# E4m.net
KiCad netlist of a schematic drawn in EAGLE
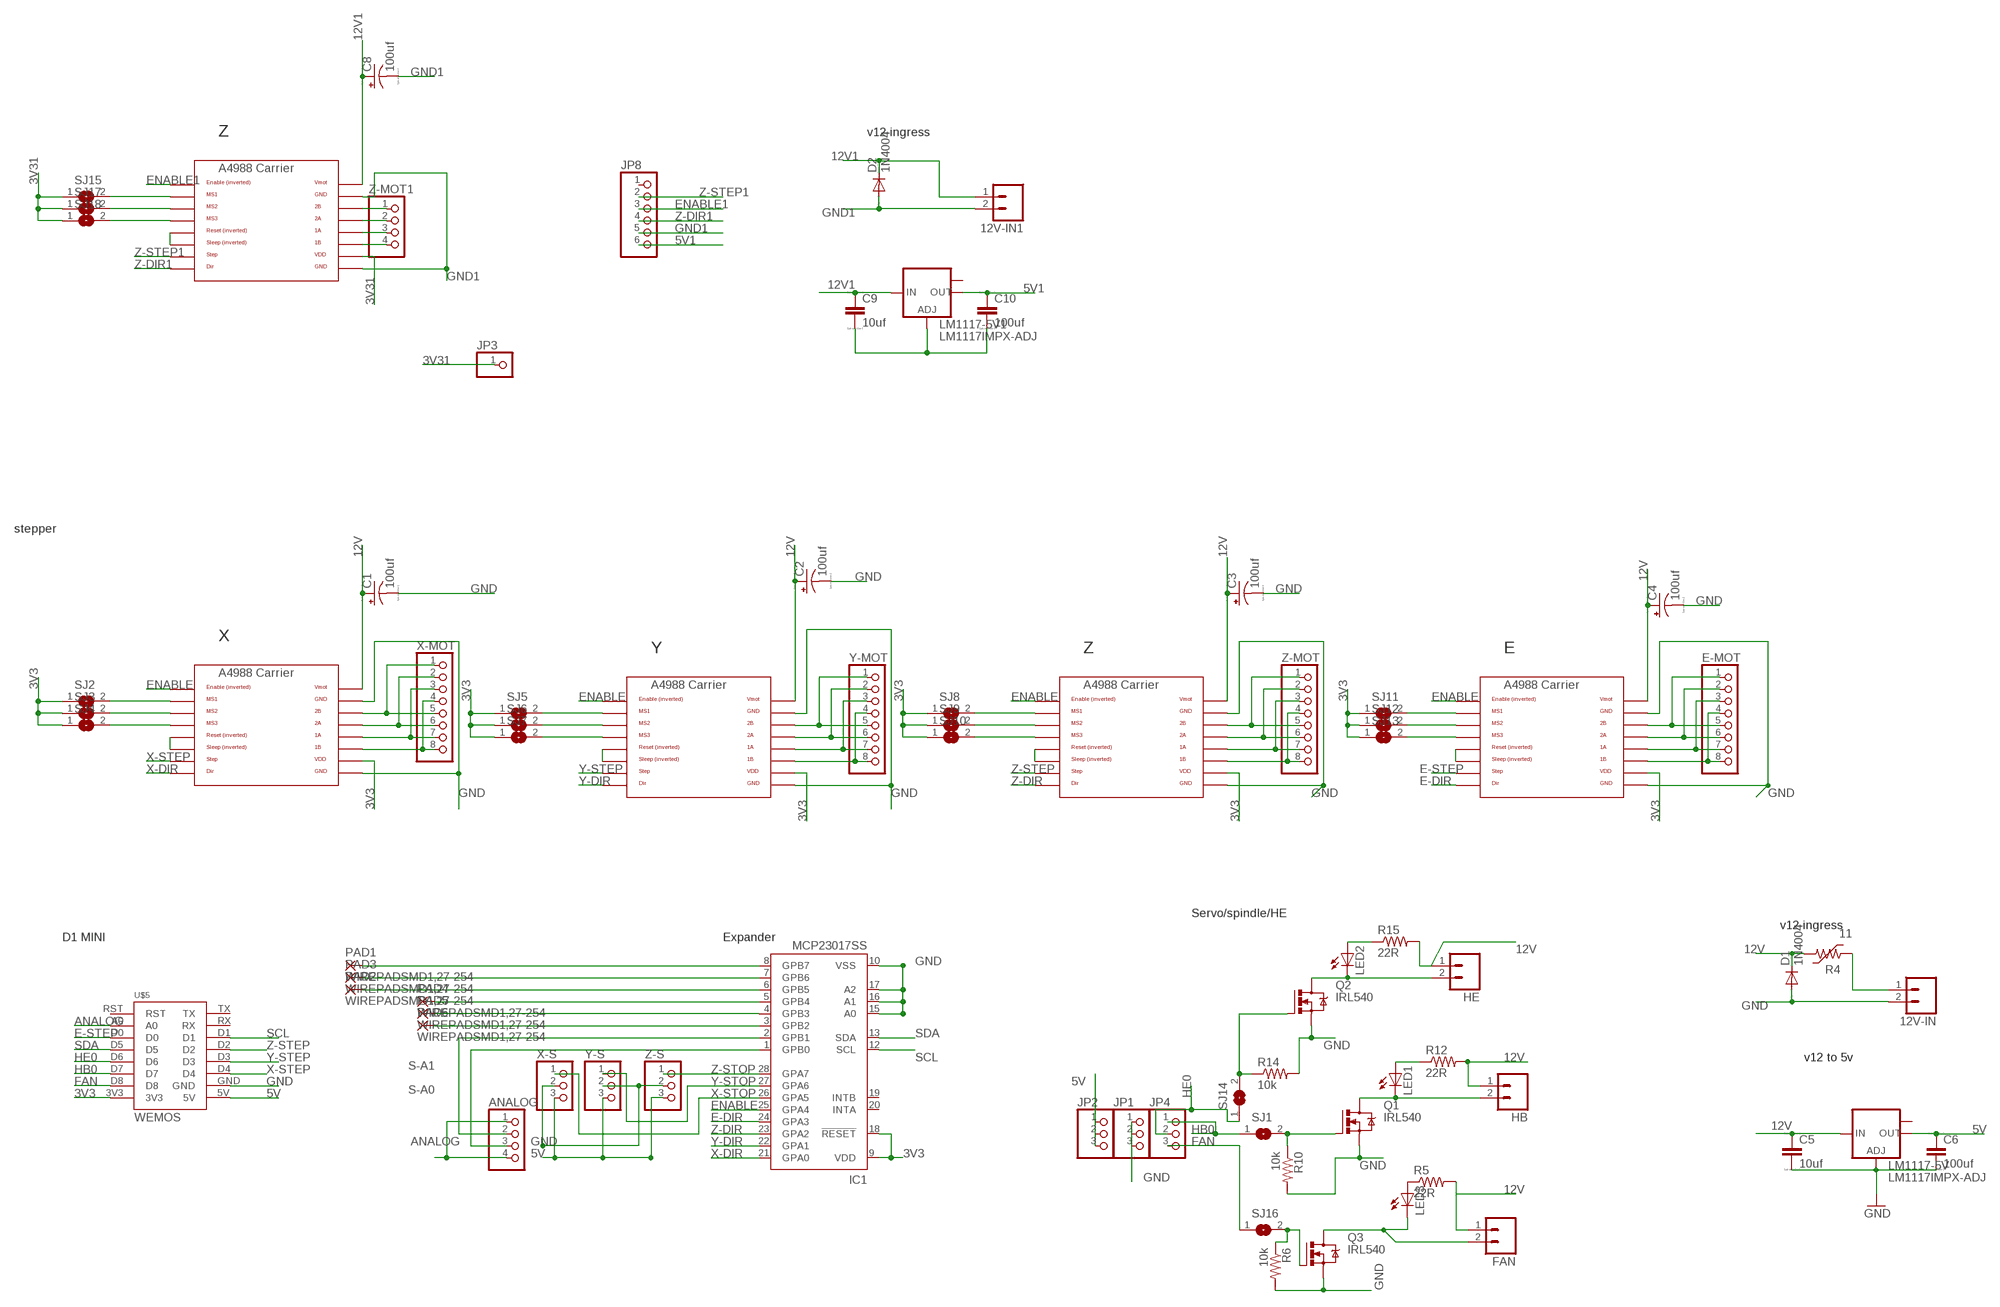
[diagram p0: schematic, sheet 1]

(export (version "E")
  (design (tool "Eeschema 10.0.6"))
  (components
    (comp (ref "12V-IN")
      (value "M02PTH")
      (footprint "eagle-import:1X02")
      (libsource (lib "eagle-import") (part "M02PTH"))
    )
    (comp (ref "12V-IN1")
      (value "M02PTH")
      (footprint "eagle-import:1X02")
      (libsource (lib "eagle-import") (part "M02PTH"))
    )
    (comp (ref "ANALOG")
      (value "PINHD-1X4")
      (footprint "eagle-import:1X04")
      (libsource (lib "eagle-import") (part "PINHD-1X4"))
    )
    (comp (ref "C1")
      (value "100uf")
      (footprint "eagle-import:153CLV-0605")
      (libsource (lib "eagle-import") (part "CPOL-US153CLV-0605"))
    )
    (comp (ref "C2")
      (value "100uf")
      (footprint "eagle-import:153CLV-0605")
      (libsource (lib "eagle-import") (part "CPOL-US153CLV-0605"))
    )
    (comp (ref "C3")
      (value "100uf")
      (footprint "eagle-import:153CLV-0605")
      (libsource (lib "eagle-import") (part "CPOL-US153CLV-0605"))
    )
    (comp (ref "C4")
      (value "100uf")
      (footprint "eagle-import:153CLV-0605")
      (libsource (lib "eagle-import") (part "CPOL-US153CLV-0605"))
    )
    (comp (ref "C5")
      (value "10uf")
      (footprint "eagle-import:C0805")
      (libsource (lib "eagle-import") (part "C"))
    )
    (comp (ref "C6")
      (value "100uf")
      (footprint "eagle-import:C0805")
      (libsource (lib "eagle-import") (part "C"))
    )
    (comp (ref "C8")
      (value "100uf")
      (footprint "eagle-import:153CLV-0605")
      (libsource (lib "eagle-import") (part "CPOL-US153CLV-0605"))
    )
    (comp (ref "C9")
      (value "10uf")
      (footprint "eagle-import:C0603")
      (libsource (lib "eagle-import") (part "CC0603"))
    )
    (comp (ref "C10")
      (value "100uf")
      (footprint "eagle-import:C0603")
      (libsource (lib "eagle-import") (part "CC0603"))
    )
    (comp (ref "D1")
      (value "1N4004")
      (footprint "eagle-import:DO41-10")
      (libsource (lib "eagle-import") (part "1N4004"))
    )
    (comp (ref "D2")
      (value "1N4004")
      (footprint "eagle-import:DO41-10")
      (libsource (lib "eagle-import") (part "1N4004"))
    )
    (comp (ref "E-MOT")
      (value "PINHD-1X8CLEANBIG")
      (footprint "eagle-import:1X08-CLEANBIG")
      (libsource (lib "eagle-import") (part "PINHD-1X8CLEANBIG"))
    )
    (comp (ref "FAN")
      (value "M02PTH")
      (footprint "eagle-import:1X02")
      (libsource (lib "eagle-import") (part "M02PTH"))
    )
    (comp (ref "HB")
      (value "M02PTH")
      (footprint "eagle-import:1X02")
      (libsource (lib "eagle-import") (part "M02PTH"))
    )
    (comp (ref "HE")
      (value "M02PTH")
      (footprint "eagle-import:1X02")
      (libsource (lib "eagle-import") (part "M02PTH"))
    )
    (comp (ref "IC1")
      (value "MCP23017SS")
      (footprint "eagle-import:SSOP28")
      (libsource (lib "eagle-import") (part "MCP23017SS"))
    )
    (comp (ref "JP1")
      (value "PINHD-1X3CB")
      (footprint "eagle-import:1X03-CLEANBIG")
      (libsource (lib "eagle-import") (part "PINHD-1X3CB"))
    )
    (comp (ref "JP2")
      (value "PINHD-1X3CB")
      (footprint "eagle-import:1X03-CLEANBIG")
      (libsource (lib "eagle-import") (part "PINHD-1X3CB"))
    )
    (comp (ref "JP3")
      (value "PINHD-1X1CB")
      (footprint "eagle-import:1X01-CLEANBIG")
      (libsource (lib "eagle-import") (part "PINHD-1X1CB"))
    )
    (comp (ref "JP4")
      (value "PINHD-1X3CB")
      (footprint "eagle-import:1X03-CLEANBIG")
      (libsource (lib "eagle-import") (part "PINHD-1X3CB"))
    )
    (comp (ref "JP8")
      (value "PINHD-1X6")
      (footprint "eagle-import:1X06")
      (libsource (lib "eagle-import") (part "PINHD-1X6"))
    )
    (comp (ref "LED1")
      (value "LEDCHIP-LED0805")
      (footprint "eagle-import:CHIP-LED0805")
      (libsource (lib "eagle-import") (part "LEDCHIP-LED0805"))
    )
    (comp (ref "LED2")
      (value "LEDCHIP-LED0805")
      (footprint "eagle-import:CHIP-LED0805")
      (libsource (lib "eagle-import") (part "LEDCHIP-LED0805"))
    )
    (comp (ref "LED3")
      (value "LEDCHIP-LED0805")
      (footprint "eagle-import:CHIP-LED0805")
      (libsource (lib "eagle-import") (part "LEDCHIP-LED0805"))
    )
    (comp (ref "LM1117-5V")
      (value "LM1117IMPX-ADJ")
      (footprint "eagle-import:SOT223")
      (libsource (lib "eagle-import") (part "LM1117IMPX-ADJ"))
    )
    (comp (ref "LM1117-5V1")
      (value "LM1117IMPX-ADJ")
      (footprint "eagle-import:SOT223")
      (libsource (lib "eagle-import") (part "LM1117IMPX-ADJ"))
    )
    (comp (ref "PAD1")
      (value "WIREPADSMD1,27-254")
      (footprint "eagle-import:SMD1,27-2,54")
      (libsource (lib "eagle-import") (part "WIREPADSMD1,27-254"))
    )
    (comp (ref "PAD2")
      (value "WIREPADSMD1,27-254")
      (footprint "eagle-import:SMD1,27-2,54")
      (libsource (lib "eagle-import") (part "WIREPADSMD1,27-254"))
    )
    (comp (ref "PAD3")
      (value "WIREPADSMD1,27-254")
      (footprint "eagle-import:SMD1,27-2,54")
      (libsource (lib "eagle-import") (part "WIREPADSMD1,27-254"))
    )
    (comp (ref "PAD4")
      (value "WIREPADSMD1,27-254")
      (footprint "eagle-import:SMD1,27-2,54")
      (libsource (lib "eagle-import") (part "WIREPADSMD1,27-254"))
    )
    (comp (ref "PAD5")
      (value "WIREPADSMD1,27-254")
      (footprint "eagle-import:SMD1,27-2,54")
      (libsource (lib "eagle-import") (part "WIREPADSMD1,27-254"))
    )
    (comp (ref "PAD6")
      (value "WIREPADSMD1,27-254")
      (footprint "eagle-import:SMD1,27-2,54")
      (libsource (lib "eagle-import") (part "WIREPADSMD1,27-254"))
    )
    (comp (ref "Q1")
      (value "IRL540")
      (footprint "eagle-import:TO220BV")
      (libsource (lib "eagle-import") (part "IRF540"))
    )
    (comp (ref "Q2")
      (value "IRL540")
      (footprint "eagle-import:TO220BV")
      (libsource (lib "eagle-import") (part "IRF540"))
    )
    (comp (ref "Q3")
      (value "IRL540")
      (footprint "eagle-import:TO220BV")
      (libsource (lib "eagle-import") (part "IRF540"))
    )
    (comp (ref "R4")
      (value "11")
      (footprint "eagle-import:PF-8.0")
      (libsource (lib "eagle-import") (part "PTC-PF-8.0"))
    )
    (comp (ref "R5")
      (value "22R")
      (footprint "eagle-import:R0805")
      (libsource (lib "eagle-import") (part "R-US_R0805"))
    )
    (comp (ref "R6")
      (value "10k")
      (footprint "eagle-import:R0805")
      (libsource (lib "eagle-import") (part "R-US_R0805"))
    )
    (comp (ref "R10")
      (value "10k")
      (footprint "eagle-import:R0805")
      (libsource (lib "eagle-import") (part "R-US_R0805"))
    )
    (comp (ref "R12")
      (value "22R")
      (footprint "eagle-import:R0805")
      (libsource (lib "eagle-import") (part "R-US_R0805"))
    )
    (comp (ref "R14")
      (value "10k")
      (footprint "eagle-import:R0805")
      (libsource (lib "eagle-import") (part "R-US_R0805"))
    )
    (comp (ref "R15")
      (value "22R")
      (footprint "eagle-import:R0805")
      (libsource (lib "eagle-import") (part "R-US_R0805"))
    )
    (comp (ref "SJ1") (value "SJ") (footprint "eagle-import:SJ") (libsource (lib "eagle-import") (part "SJ")))
    (comp (ref "SJ2") (value "SJ") (footprint "eagle-import:SJ") (libsource (lib "eagle-import") (part "SJ")))
    (comp (ref "SJ3") (value "SJ") (footprint "eagle-import:SJ") (libsource (lib "eagle-import") (part "SJ")))
    (comp (ref "SJ4") (value "SJ") (footprint "eagle-import:SJ") (libsource (lib "eagle-import") (part "SJ")))
    (comp (ref "SJ5") (value "SJ") (footprint "eagle-import:SJ") (libsource (lib "eagle-import") (part "SJ")))
    (comp (ref "SJ6") (value "SJ") (footprint "eagle-import:SJ") (libsource (lib "eagle-import") (part "SJ")))
    (comp (ref "SJ7") (value "SJ") (footprint "eagle-import:SJ") (libsource (lib "eagle-import") (part "SJ")))
    (comp (ref "SJ8") (value "SJ") (footprint "eagle-import:SJ") (libsource (lib "eagle-import") (part "SJ")))
    (comp (ref "SJ9") (value "SJ") (footprint "eagle-import:SJ") (libsource (lib "eagle-import") (part "SJ")))
    (comp (ref "SJ10")
      (value "SJ")
      (footprint "eagle-import:SJ")
      (libsource (lib "eagle-import") (part "SJ"))
    )
    (comp (ref "SJ11")
      (value "SJ")
      (footprint "eagle-import:SJ")
      (libsource (lib "eagle-import") (part "SJ"))
    )
    (comp (ref "SJ12")
      (value "SJ")
      (footprint "eagle-import:SJ")
      (libsource (lib "eagle-import") (part "SJ"))
    )
    (comp (ref "SJ13")
      (value "SJ")
      (footprint "eagle-import:SJ")
      (libsource (lib "eagle-import") (part "SJ"))
    )
    (comp (ref "SJ14")
      (value "SJ")
      (footprint "eagle-import:SJ")
      (libsource (lib "eagle-import") (part "SJ"))
    )
    (comp (ref "SJ15")
      (value "SJ")
      (footprint "eagle-import:SJ")
      (libsource (lib "eagle-import") (part "SJ"))
    )
    (comp (ref "SJ16")
      (value "SJ")
      (footprint "eagle-import:SJ")
      (libsource (lib "eagle-import") (part "SJ"))
    )
    (comp (ref "SJ17")
      (value "SJ")
      (footprint "eagle-import:SJ")
      (libsource (lib "eagle-import") (part "SJ"))
    )
    (comp (ref "SJ18")
      (value "SJ")
      (footprint "eagle-import:SJ")
      (libsource (lib "eagle-import") (part "SJ"))
    )
    (comp (ref "U$1")
      (value "A4988BREAKOUT")
      (footprint "eagle-import:A4988BREAKOUT")
      (libsource (lib "eagle-import") (part "A4988BREAKOUT"))
    )
    (comp (ref "U$2")
      (value "A4988BREAKOUT")
      (footprint "eagle-import:A4988BREAKOUT")
      (libsource (lib "eagle-import") (part "A4988BREAKOUT"))
    )
    (comp (ref "U$3")
      (value "A4988BREAKOUT")
      (footprint "eagle-import:A4988BREAKOUT")
      (libsource (lib "eagle-import") (part "A4988BREAKOUT"))
    )
    (comp (ref "U$5")
      (value "WEMOS")
      (footprint "eagle-import:WEMOS")
      (libsource (lib "eagle-import") (part "WEMOS"))
    )
    (comp (ref "U$6")
      (value "A4988BREAKOUT")
      (footprint "eagle-import:A4988BREAKOUT")
      (libsource (lib "eagle-import") (part "A4988BREAKOUT"))
    )
    (comp (ref "U$9")
      (value "A4988BREAKOUT")
      (footprint "eagle-import:A4988BREAKOUT")
      (libsource (lib "eagle-import") (part "A4988BREAKOUT"))
    )
    (comp (ref "X-MOT")
      (value "PINHD-1X8CLEANBIG")
      (footprint "eagle-import:1X08-CLEANBIG")
      (libsource (lib "eagle-import") (part "PINHD-1X8CLEANBIG"))
    )
    (comp (ref "X-S")
      (value "PINHD-1X3CB")
      (footprint "eagle-import:1X03-CLEANBIG")
      (libsource (lib "eagle-import") (part "PINHD-1X3CB"))
    )
    (comp (ref "Y-MOT")
      (value "PINHD-1X8CLEANBIG")
      (footprint "eagle-import:1X08-CLEANBIG")
      (libsource (lib "eagle-import") (part "PINHD-1X8CLEANBIG"))
    )
    (comp (ref "Y-S")
      (value "PINHD-1X3CB")
      (footprint "eagle-import:1X03-CLEANBIG")
      (libsource (lib "eagle-import") (part "PINHD-1X3CB"))
    )
    (comp (ref "Z-MOT")
      (value "PINHD-1X8CLEANBIG")
      (footprint "eagle-import:1X08-CLEANBIG")
      (libsource (lib "eagle-import") (part "PINHD-1X8CLEANBIG"))
    )
    (comp (ref "Z-MOT1")
      (value "PINHD-1X4")
      (footprint "eagle-import:1X04")
      (libsource (lib "eagle-import") (part "PINHD-1X4"))
    )
    (comp (ref "Z-S")
      (value "PINHD-1X3CB")
      (footprint "eagle-import:1X03-CLEANBIG")
      (libsource (lib "eagle-import") (part "PINHD-1X3CB"))
    )
  )
  (nets
    (net (code "1") (name "/3V3") (class "Default")
      (node (ref "IC1") (pin "18") (pinfunction "~{RESET}_18") (pintype "input"))
      (node (ref "IC1") (pin "9") (pinfunction "VDD_9") (pintype "power_in"))
      (node (ref "SJ10") (pin "1") (pinfunction "1_1") (pintype "passive"))
      (node (ref "SJ11") (pin "1") (pinfunction "1_1") (pintype "passive"))
      (node (ref "SJ12") (pin "1") (pinfunction "1_1") (pintype "passive"))
      (node (ref "SJ13") (pin "1") (pinfunction "1_1") (pintype "passive"))
      (node (ref "SJ2") (pin "1") (pinfunction "1_1") (pintype "passive"))
      (node (ref "SJ3") (pin "1") (pinfunction "1_1") (pintype "passive"))
      (node (ref "SJ4") (pin "1") (pinfunction "1_1") (pintype "passive"))
      (node (ref "SJ5") (pin "1") (pinfunction "1_1") (pintype "passive"))
      (node (ref "SJ6") (pin "1") (pinfunction "1_1") (pintype "passive"))
      (node (ref "SJ7") (pin "1") (pinfunction "1_1") (pintype "passive"))
      (node (ref "SJ8") (pin "1") (pinfunction "1_1") (pintype "passive"))
      (node (ref "SJ9") (pin "1") (pinfunction "1_1") (pintype "passive"))
      (node (ref "U$1") (pin "VDD") (pinfunction "VDD_VDD") (pintype "power_in"))
      (node (ref "U$2") (pin "VDD") (pinfunction "VDD_VDD") (pintype "power_in"))
      (node (ref "U$3") (pin "VDD") (pinfunction "VDD_VDD") (pintype "power_in"))
      (node (ref "U$5") (pin "3V3") (pinfunction "3V3_3V3") (pintype "bidirectional"))
      (node (ref "U$9") (pin "VDD") (pinfunction "VDD_VDD") (pintype "power_in"))
    )
    (net (code "2") (name "/3V31") (class "Default")
      (node (ref "JP3") (pin "1") (pinfunction "1_1") (pintype "passive"))
      (node (ref "SJ15") (pin "1") (pinfunction "1_1") (pintype "passive"))
      (node (ref "SJ17") (pin "1") (pinfunction "1_1") (pintype "passive"))
      (node (ref "SJ18") (pin "1") (pinfunction "1_1") (pintype "passive"))
      (node (ref "U$6") (pin "VDD") (pinfunction "VDD_VDD") (pintype "power_in"))
    )
    (net (code "3") (name "/5V") (class "Default")
      (node (ref "C6") (pin "1") (pinfunction "1_1") (pintype "passive"))
      (node (ref "JP2") (pin "1") (pinfunction "1_1") (pintype "passive"))
      (node (ref "JP2") (pin "2") (pinfunction "2_2") (pintype "passive"))
      (node (ref "JP2") (pin "3") (pinfunction "3_3") (pintype "passive"))
      (node (ref "LM1117-5V") (pin "2") (pinfunction "OUT_2") (pintype "passive"))
      (node (ref "U$5") (pin "5V") (pinfunction "5V_5V") (pintype "bidirectional"))
      (node (ref "X-S") (pin "3") (pinfunction "3_3") (pintype "passive"))
      (node (ref "Y-S") (pin "3") (pinfunction "3_3") (pintype "passive"))
      (node (ref "Z-S") (pin "3") (pinfunction "3_3") (pintype "passive"))
    )
    (net (code "4") (name "/5V1") (class "Default")
      (node (ref "C10") (pin "1") (pinfunction "1_1") (pintype "passive"))
      (node (ref "JP8") (pin "6") (pinfunction "6_6") (pintype "passive"))
      (node (ref "LM1117-5V1") (pin "2") (pinfunction "OUT_2") (pintype "passive"))
    )
    (net (code "5") (name "/12V") (class "Default")
      (node (ref "C1") (pin "+") (pinfunction "+_+") (pintype "passive"))
      (node (ref "C2") (pin "+") (pinfunction "+_+") (pintype "passive"))
      (node (ref "C3") (pin "+") (pinfunction "+_+") (pintype "passive"))
      (node (ref "C4") (pin "+") (pinfunction "+_+") (pintype "passive"))
      (node (ref "C5") (pin "1") (pinfunction "1_1") (pintype "passive"))
      (node (ref "D1") (pin "C") (pinfunction "C_C") (pintype "passive"))
      (node (ref "FAN") (pin "1") (pinfunction "1_1") (pintype "passive"))
      (node (ref "HB") (pin "1") (pinfunction "1_1") (pintype "passive"))
      (node (ref "HE") (pin "1") (pinfunction "1_1") (pintype "passive"))
      (node (ref "LM1117-5V") (pin "3") (pinfunction "IN_3") (pintype "input"))
      (node (ref "R12") (pin "2") (pinfunction "2_2") (pintype "passive"))
      (node (ref "R15") (pin "2") (pinfunction "2_2") (pintype "passive"))
      (node (ref "R4") (pin "2") (pinfunction "2_2") (pintype "passive"))
      (node (ref "R5") (pin "2") (pinfunction "2_2") (pintype "passive"))
      (node (ref "U$1") (pin "VMOT") (pinfunction "VMOT_VMOT") (pintype "power_in"))
      (node (ref "U$2") (pin "VMOT") (pinfunction "VMOT_VMOT") (pintype "power_in"))
      (node (ref "U$3") (pin "VMOT") (pinfunction "VMOT_VMOT") (pintype "power_in"))
      (node (ref "U$9") (pin "VMOT") (pinfunction "VMOT_VMOT") (pintype "power_in"))
    )
    (net (code "6") (name "/12V1") (class "Default")
      (node (ref "12V-IN1") (pin "1") (pinfunction "1_1") (pintype "passive"))
      (node (ref "C8") (pin "+") (pinfunction "+_+") (pintype "passive"))
      (node (ref "C9") (pin "1") (pinfunction "1_1") (pintype "passive"))
      (node (ref "D2") (pin "C") (pinfunction "C_C") (pintype "passive"))
      (node (ref "LM1117-5V1") (pin "3") (pinfunction "IN_3") (pintype "input"))
      (node (ref "U$6") (pin "VMOT") (pinfunction "VMOT_VMOT") (pintype "power_in"))
    )
    (net (code "7") (name "/ANALOG") (class "Default")
      (node (ref "ANALOG") (pin "1") (pinfunction "1_1") (pintype "passive"))
      (node (ref "ANALOG") (pin "4") (pinfunction "4_4") (pintype "passive"))
      (node (ref "U$5") (pin "A0") (pinfunction "A0_A0") (pintype "bidirectional"))
    )
    (net (code "8") (name "/E-DIR") (class "Default")
      (node (ref "IC1") (pin "24") (pinfunction "GPA3_24") (pintype "bidirectional"))
      (node (ref "U$2") (pin "DIR") (pinfunction "DIR_DIR") (pintype "input"))
    )
    (net (code "9") (name "/E-STEP") (class "Default")
      (node (ref "U$2") (pin "STEP") (pinfunction "STEP_STEP") (pintype "input"))
      (node (ref "U$5") (pin "D0") (pinfunction "D0_D0") (pintype "bidirectional"))
    )
    (net (code "10") (name "/ENABLE") (class "Default")
      (node (ref "IC1") (pin "25") (pinfunction "GPA4_25") (pintype "bidirectional"))
      (node (ref "U$1") (pin "EN") (pinfunction "EN_EN") (pintype "input"))
      (node (ref "U$2") (pin "EN") (pinfunction "EN_EN") (pintype "input"))
      (node (ref "U$3") (pin "EN") (pinfunction "EN_EN") (pintype "input"))
      (node (ref "U$9") (pin "EN") (pinfunction "EN_EN") (pintype "input"))
    )
    (net (code "11") (name "/ENABLE1") (class "Default")
      (node (ref "JP8") (pin "3") (pinfunction "3_3") (pintype "passive"))
      (node (ref "U$6") (pin "EN") (pinfunction "EN_EN") (pintype "input"))
    )
    (net (code "12") (name "/FAN") (class "Default")
      (node (ref "JP4") (pin "3") (pinfunction "3_3") (pintype "passive"))
      (node (ref "SJ16") (pin "1") (pinfunction "1_1") (pintype "passive"))
      (node (ref "U$5") (pin "D8") (pinfunction "D8_D8") (pintype "bidirectional"))
    )
    (net (code "13") (name "/GND1") (class "Default")
      (node (ref "12V-IN1") (pin "2") (pinfunction "2_2") (pintype "passive"))
      (node (ref "C8") (pin "-") (pinfunction "-_-") (pintype "passive"))
      (node (ref "D2") (pin "A") (pinfunction "A_A") (pintype "passive"))
      (node (ref "JP8") (pin "5") (pinfunction "5_5") (pintype "passive"))
      (node (ref "U$6") (pin "GND") (pinfunction "GND_GND") (pintype "power_in"))
      (node (ref "U$6") (pin "GND@0") (pinfunction "GND_GND@0") (pintype "power_in"))
    )
    (net (code "14") (name "/HB0") (class "Default")
      (node (ref "JP4") (pin "1") (pinfunction "1_1") (pintype "passive"))
      (node (ref "SJ1") (pin "1") (pinfunction "1_1") (pintype "passive"))
      (node (ref "U$5") (pin "D7") (pinfunction "D7_D7") (pintype "bidirectional"))
    )
    (net (code "15") (name "/HE0") (class "Default")
      (node (ref "JP4") (pin "2") (pinfunction "2_2") (pintype "passive"))
      (node (ref "SJ14") (pin "1") (pinfunction "1_1") (pintype "passive"))
      (node (ref "U$5") (pin "D6") (pinfunction "D6_D6") (pintype "bidirectional"))
    )
    (net (code "16") (name "/S-A0") (class "Default")
      (node (ref "ANALOG") (pin "3") (pinfunction "3_3") (pintype "passive"))
      (node (ref "IC1") (pin "1") (pinfunction "GPB0_1") (pintype "bidirectional"))
    )
    (net (code "17") (name "/S-A1") (class "Default")
      (node (ref "ANALOG") (pin "2") (pinfunction "2_2") (pintype "passive"))
      (node (ref "IC1") (pin "2") (pinfunction "GPB1_2") (pintype "bidirectional"))
    )
    (net (code "18") (name "/SCL") (class "Default")
      (node (ref "IC1") (pin "12") (pinfunction "SCL_12") (pintype "input"))
      (node (ref "U$5") (pin "D1") (pinfunction "D1_D1") (pintype "bidirectional"))
    )
    (net (code "19") (name "/SDA") (class "Default")
      (node (ref "IC1") (pin "13") (pinfunction "SDA_13") (pintype "bidirectional"))
      (node (ref "U$5") (pin "D5") (pinfunction "D5_D5") (pintype "bidirectional"))
    )
    (net (code "20") (name "/X-DIR") (class "Default")
      (node (ref "IC1") (pin "21") (pinfunction "GPA0_21") (pintype "bidirectional"))
      (node (ref "U$1") (pin "DIR") (pinfunction "DIR_DIR") (pintype "input"))
    )
    (net (code "21") (name "/X-STEP") (class "Default")
      (node (ref "U$1") (pin "STEP") (pinfunction "STEP_STEP") (pintype "input"))
      (node (ref "U$5") (pin "D4") (pinfunction "D4_D4") (pintype "bidirectional"))
    )
    (net (code "22") (name "/X-STOP") (class "Default")
      (node (ref "IC1") (pin "26") (pinfunction "GPA5_26") (pintype "bidirectional"))
      (node (ref "X-S") (pin "1") (pinfunction "1_1") (pintype "passive"))
    )
    (net (code "23") (name "/Y-DIR") (class "Default")
      (node (ref "IC1") (pin "22") (pinfunction "GPA1_22") (pintype "bidirectional"))
      (node (ref "U$3") (pin "DIR") (pinfunction "DIR_DIR") (pintype "input"))
    )
    (net (code "24") (name "/Y-STEP") (class "Default")
      (node (ref "U$3") (pin "STEP") (pinfunction "STEP_STEP") (pintype "input"))
      (node (ref "U$5") (pin "D3") (pinfunction "D3_D3") (pintype "bidirectional"))
    )
    (net (code "25") (name "/Y-STOP") (class "Default")
      (node (ref "IC1") (pin "27") (pinfunction "GPA6_27") (pintype "bidirectional"))
      (node (ref "Y-S") (pin "1") (pinfunction "1_1") (pintype "passive"))
    )
    (net (code "26") (name "/Z-DIR") (class "Default")
      (node (ref "IC1") (pin "23") (pinfunction "GPA2_23") (pintype "bidirectional"))
      (node (ref "U$9") (pin "DIR") (pinfunction "DIR_DIR") (pintype "input"))
    )
    (net (code "27") (name "/Z-DIR1") (class "Default")
      (node (ref "JP8") (pin "4") (pinfunction "4_4") (pintype "passive"))
      (node (ref "U$6") (pin "DIR") (pinfunction "DIR_DIR") (pintype "input"))
    )
    (net (code "28") (name "/Z-STEP") (class "Default")
      (node (ref "U$5") (pin "D2") (pinfunction "D2_D2") (pintype "bidirectional"))
      (node (ref "U$9") (pin "STEP") (pinfunction "STEP_STEP") (pintype "input"))
    )
    (net (code "29") (name "/Z-STEP1") (class "Default")
      (node (ref "JP8") (pin "2") (pinfunction "2_2") (pintype "passive"))
      (node (ref "U$6") (pin "STEP") (pinfunction "STEP_STEP") (pintype "input"))
    )
    (net (code "30") (name "/Z-STOP") (class "Default")
      (node (ref "IC1") (pin "28") (pinfunction "GPA7_28") (pintype "bidirectional"))
      (node (ref "Z-S") (pin "1") (pinfunction "1_1") (pintype "passive"))
    )
    (net (code "31") (name "GND") (class "Default")
      (node (ref "12V-IN") (pin "2") (pinfunction "2_2") (pintype "passive"))
      (node (ref "C1") (pin "-") (pinfunction "-_-") (pintype "passive"))
      (node (ref "C2") (pin "-") (pinfunction "-_-") (pintype "passive"))
      (node (ref "C3") (pin "-") (pinfunction "-_-") (pintype "passive"))
      (node (ref "C4") (pin "-") (pinfunction "-_-") (pintype "passive"))
      (node (ref "C5") (pin "2") (pinfunction "2_2") (pintype "passive"))
      (node (ref "C6") (pin "2") (pinfunction "2_2") (pintype "passive"))
      (node (ref "D1") (pin "A") (pinfunction "A_A") (pintype "passive"))
      (node (ref "IC1") (pin "10") (pinfunction "VSS_10") (pintype "power_in"))
      (node (ref "IC1") (pin "15") (pinfunction "A0_15") (pintype "input"))
      (node (ref "IC1") (pin "16") (pinfunction "A1_16") (pintype "input"))
      (node (ref "IC1") (pin "17") (pinfunction "A2_17") (pintype "input"))
      (node (ref "JP1") (pin "1") (pinfunction "1_1") (pintype "passive"))
      (node (ref "JP1") (pin "2") (pinfunction "2_2") (pintype "passive"))
      (node (ref "JP1") (pin "3") (pinfunction "3_3") (pintype "passive"))
      (node (ref "LM1117-5V") (pin "1") (pinfunction "ADJ_1") (pintype "input"))
      (node (ref "Q1") (pin "S") (pinfunction "S_S") (pintype "passive"))
      (node (ref "Q2") (pin "S") (pinfunction "S_S") (pintype "passive"))
      (node (ref "Q3") (pin "S") (pinfunction "S_S") (pintype "passive"))
      (node (ref "R10") (pin "2") (pinfunction "2_2") (pintype "passive"))
      (node (ref "R14") (pin "2") (pinfunction "2_2") (pintype "passive"))
      (node (ref "R6") (pin "2") (pinfunction "2_2") (pintype "passive"))
      (node (ref "U$1") (pin "GND") (pinfunction "GND_GND") (pintype "power_in"))
      (node (ref "U$1") (pin "GND@0") (pinfunction "GND_GND@0") (pintype "power_in"))
      (node (ref "U$2") (pin "GND") (pinfunction "GND_GND") (pintype "power_in"))
      (node (ref "U$2") (pin "GND@0") (pinfunction "GND_GND@0") (pintype "power_in"))
      (node (ref "U$3") (pin "GND") (pinfunction "GND_GND") (pintype "power_in"))
      (node (ref "U$3") (pin "GND@0") (pinfunction "GND_GND@0") (pintype "power_in"))
      (node (ref "U$5") (pin "GND") (pinfunction "GND_GND") (pintype "bidirectional"))
      (node (ref "U$9") (pin "GND") (pinfunction "GND_GND") (pintype "power_in"))
      (node (ref "U$9") (pin "GND@0") (pinfunction "GND_GND@0") (pintype "power_in"))
      (node (ref "X-S") (pin "2") (pinfunction "2_2") (pintype "passive"))
      (node (ref "Y-S") (pin "2") (pinfunction "2_2") (pintype "passive"))
      (node (ref "Z-S") (pin "2") (pinfunction "2_2") (pintype "passive"))
    )
    (net (code "32") (name "Net-(12V-IN-Pad1)") (class "Default")
      (node (ref "12V-IN") (pin "1") (pinfunction "1_1") (pintype "passive"))
      (node (ref "R4") (pin "1") (pinfunction "1_1") (pintype "passive"))
    )
    (net (code "33") (name "Net-(E-MOT-Pad1)") (class "Default")
      (node (ref "E-MOT") (pin "1") (pinfunction "1_1") (pintype "passive"))
      (node (ref "E-MOT") (pin "5") (pinfunction "5_5") (pintype "passive"))
      (node (ref "U$2") (pin "2B") (pinfunction "2B_2B") (pintype "output"))
    )
    (net (code "34") (name "Net-(E-MOT-Pad2)") (class "Default")
      (node (ref "E-MOT") (pin "2") (pinfunction "2_2") (pintype "passive"))
      (node (ref "E-MOT") (pin "6") (pinfunction "6_6") (pintype "passive"))
      (node (ref "U$2") (pin "2A") (pinfunction "2A_2A") (pintype "output"))
    )
    (net (code "35") (name "Net-(E-MOT-Pad3)") (class "Default")
      (node (ref "E-MOT") (pin "3") (pinfunction "3_3") (pintype "passive"))
      (node (ref "E-MOT") (pin "7") (pinfunction "7_7") (pintype "passive"))
      (node (ref "U$2") (pin "1A") (pinfunction "1A_1A") (pintype "output"))
    )
    (net (code "36") (name "Net-(E-MOT-Pad4)") (class "Default")
      (node (ref "E-MOT") (pin "4") (pinfunction "4_4") (pintype "passive"))
      (node (ref "E-MOT") (pin "8") (pinfunction "8_8") (pintype "passive"))
      (node (ref "U$2") (pin "1B") (pinfunction "1B_1B") (pintype "output"))
    )
    (net (code "37") (name "Net-(FAN-Pad2)") (class "Default")
      (node (ref "FAN") (pin "2") (pinfunction "2_2") (pintype "passive"))
      (node (ref "LED3") (pin "C") (pinfunction "C_C") (pintype "passive"))
      (node (ref "Q3") (pin "D") (pinfunction "D_D") (pintype "passive"))
    )
    (net (code "38") (name "Net-(HB-Pad2)") (class "Default")
      (node (ref "HB") (pin "2") (pinfunction "2_2") (pintype "passive"))
      (node (ref "LED1") (pin "C") (pinfunction "C_C") (pintype "passive"))
      (node (ref "Q1") (pin "D") (pinfunction "D_D") (pintype "passive"))
    )
    (net (code "39") (name "Net-(HE-Pad2)") (class "Default")
      (node (ref "HE") (pin "2") (pinfunction "2_2") (pintype "passive"))
      (node (ref "LED2") (pin "C") (pinfunction "C_C") (pintype "passive"))
      (node (ref "Q2") (pin "D") (pinfunction "D_D") (pintype "passive"))
    )
    (net (code "40") (name "Net-(IC1-GPB2)") (class "Default")
      (node (ref "IC1") (pin "3") (pinfunction "GPB2_3") (pintype "bidirectional"))
      (node (ref "PAD6") (pin "1") (pinfunction "P_1") (pintype "passive"))
    )
    (net (code "41") (name "Net-(IC1-GPB3)") (class "Default")
      (node (ref "IC1") (pin "4") (pinfunction "GPB3_4") (pintype "bidirectional"))
      (node (ref "PAD5") (pin "1") (pinfunction "P_1") (pintype "passive"))
    )
    (net (code "42") (name "Net-(IC1-GPB4)") (class "Default")
      (node (ref "IC1") (pin "5") (pinfunction "GPB4_5") (pintype "bidirectional"))
      (node (ref "PAD4") (pin "1") (pinfunction "P_1") (pintype "passive"))
    )
    (net (code "43") (name "Net-(IC1-GPB5)") (class "Default")
      (node (ref "IC1") (pin "6") (pinfunction "GPB5_6") (pintype "bidirectional"))
      (node (ref "PAD2") (pin "1") (pinfunction "P_1") (pintype "passive"))
    )
    (net (code "44") (name "Net-(IC1-GPB6)") (class "Default")
      (node (ref "IC1") (pin "7") (pinfunction "GPB6_7") (pintype "bidirectional"))
      (node (ref "PAD3") (pin "1") (pinfunction "P_1") (pintype "passive"))
    )
    (net (code "45") (name "Net-(IC1-GPB7)") (class "Default")
      (node (ref "IC1") (pin "8") (pinfunction "GPB7_8") (pintype "bidirectional"))
      (node (ref "PAD1") (pin "1") (pinfunction "P_1") (pintype "passive"))
    )
    (net (code "46") (name "Net-(LED1-PadA)") (class "Default")
      (node (ref "LED1") (pin "A") (pinfunction "A_A") (pintype "passive"))
      (node (ref "R12") (pin "1") (pinfunction "1_1") (pintype "passive"))
    )
    (net (code "47") (name "Net-(LED2-PadA)") (class "Default")
      (node (ref "LED2") (pin "A") (pinfunction "A_A") (pintype "passive"))
      (node (ref "R15") (pin "1") (pinfunction "1_1") (pintype "passive"))
    )
    (net (code "48") (name "Net-(LED3-PadA)") (class "Default")
      (node (ref "LED3") (pin "A") (pinfunction "A_A") (pintype "passive"))
      (node (ref "R5") (pin "1") (pinfunction "1_1") (pintype "passive"))
    )
    (net (code "49") (name "Net-(LM1117-5V1-ADJ)") (class "Default")
      (node (ref "C10") (pin "2") (pinfunction "2_2") (pintype "passive"))
      (node (ref "C9") (pin "2") (pinfunction "2_2") (pintype "passive"))
      (node (ref "LM1117-5V1") (pin "1") (pinfunction "ADJ_1") (pintype "input"))
    )
    (net (code "50") (name "Net-(Q1-PadG)") (class "Default")
      (node (ref "Q1") (pin "G") (pinfunction "G_G") (pintype "passive"))
      (node (ref "R10") (pin "1") (pinfunction "1_1") (pintype "passive"))
      (node (ref "SJ1") (pin "2") (pinfunction "2_2") (pintype "passive"))
    )
    (net (code "51") (name "Net-(Q2-PadG)") (class "Default")
      (node (ref "Q2") (pin "G") (pinfunction "G_G") (pintype "passive"))
      (node (ref "R14") (pin "1") (pinfunction "1_1") (pintype "passive"))
      (node (ref "SJ14") (pin "2") (pinfunction "2_2") (pintype "passive"))
    )
    (net (code "52") (name "Net-(Q3-PadG)") (class "Default")
      (node (ref "Q3") (pin "G") (pinfunction "G_G") (pintype "passive"))
      (node (ref "R6") (pin "1") (pinfunction "1_1") (pintype "passive"))
      (node (ref "SJ16") (pin "2") (pinfunction "2_2") (pintype "passive"))
    )
    (net (code "53") (name "Net-(SJ2-Pad2)") (class "Default")
      (node (ref "SJ2") (pin "2") (pinfunction "2_2") (pintype "passive"))
      (node (ref "U$1") (pin "MS1") (pinfunction "MS1_MS1") (pintype "input"))
    )
    (net (code "54") (name "Net-(SJ3-Pad2)") (class "Default")
      (node (ref "SJ3") (pin "2") (pinfunction "2_2") (pintype "passive"))
      (node (ref "U$1") (pin "MS2") (pinfunction "MS2_MS2") (pintype "input"))
    )
    (net (code "55") (name "Net-(SJ4-Pad2)") (class "Default")
      (node (ref "SJ4") (pin "2") (pinfunction "2_2") (pintype "passive"))
      (node (ref "U$1") (pin "MS3") (pinfunction "MS3_MS3") (pintype "input"))
    )
    (net (code "56") (name "Net-(SJ5-Pad2)") (class "Default")
      (node (ref "SJ5") (pin "2") (pinfunction "2_2") (pintype "passive"))
      (node (ref "U$3") (pin "MS1") (pinfunction "MS1_MS1") (pintype "input"))
    )
    (net (code "57") (name "Net-(SJ6-Pad2)") (class "Default")
      (node (ref "SJ6") (pin "2") (pinfunction "2_2") (pintype "passive"))
      (node (ref "U$3") (pin "MS2") (pinfunction "MS2_MS2") (pintype "input"))
    )
    (net (code "58") (name "Net-(SJ7-Pad2)") (class "Default")
      (node (ref "SJ7") (pin "2") (pinfunction "2_2") (pintype "passive"))
      (node (ref "U$3") (pin "MS3") (pinfunction "MS3_MS3") (pintype "input"))
    )
    (net (code "59") (name "Net-(SJ8-Pad2)") (class "Default")
      (node (ref "SJ8") (pin "2") (pinfunction "2_2") (pintype "passive"))
      (node (ref "U$9") (pin "MS1") (pinfunction "MS1_MS1") (pintype "input"))
    )
    (net (code "60") (name "Net-(SJ9-Pad2)") (class "Default")
      (node (ref "SJ9") (pin "2") (pinfunction "2_2") (pintype "passive"))
      (node (ref "U$9") (pin "MS2") (pinfunction "MS2_MS2") (pintype "input"))
    )
    (net (code "61") (name "Net-(SJ10-Pad2)") (class "Default")
      (node (ref "SJ10") (pin "2") (pinfunction "2_2") (pintype "passive"))
      (node (ref "U$9") (pin "MS3") (pinfunction "MS3_MS3") (pintype "input"))
    )
    (net (code "62") (name "Net-(SJ11-Pad2)") (class "Default")
      (node (ref "SJ11") (pin "2") (pinfunction "2_2") (pintype "passive"))
      (node (ref "U$2") (pin "MS1") (pinfunction "MS1_MS1") (pintype "input"))
    )
    (net (code "63") (name "Net-(SJ12-Pad2)") (class "Default")
      (node (ref "SJ12") (pin "2") (pinfunction "2_2") (pintype "passive"))
      (node (ref "U$2") (pin "MS2") (pinfunction "MS2_MS2") (pintype "input"))
    )
    (net (code "64") (name "Net-(SJ13-Pad2)") (class "Default")
      (node (ref "SJ13") (pin "2") (pinfunction "2_2") (pintype "passive"))
      (node (ref "U$2") (pin "MS3") (pinfunction "MS3_MS3") (pintype "input"))
    )
    (net (code "65") (name "Net-(SJ15-Pad2)") (class "Default")
      (node (ref "SJ15") (pin "2") (pinfunction "2_2") (pintype "passive"))
      (node (ref "U$6") (pin "MS1") (pinfunction "MS1_MS1") (pintype "input"))
    )
    (net (code "66") (name "Net-(SJ17-Pad2)") (class "Default")
      (node (ref "SJ17") (pin "2") (pinfunction "2_2") (pintype "passive"))
      (node (ref "U$6") (pin "MS2") (pinfunction "MS2_MS2") (pintype "input"))
    )
    (net (code "67") (name "Net-(SJ18-Pad2)") (class "Default")
      (node (ref "SJ18") (pin "2") (pinfunction "2_2") (pintype "passive"))
      (node (ref "U$6") (pin "MS3") (pinfunction "MS3_MS3") (pintype "input"))
    )
    (net (code "68") (name "Net-(U$1-Pad1A)") (class "Default")
      (node (ref "U$1") (pin "1A") (pinfunction "1A_1A") (pintype "output"))
      (node (ref "X-MOT") (pin "3") (pinfunction "3_3") (pintype "passive"))
      (node (ref "X-MOT") (pin "7") (pinfunction "7_7") (pintype "passive"))
    )
    (net (code "69") (name "Net-(U$1-Pad1B)") (class "Default")
      (node (ref "U$1") (pin "1B") (pinfunction "1B_1B") (pintype "output"))
      (node (ref "X-MOT") (pin "4") (pinfunction "4_4") (pintype "passive"))
      (node (ref "X-MOT") (pin "8") (pinfunction "8_8") (pintype "passive"))
    )
    (net (code "70") (name "Net-(U$1-Pad2A)") (class "Default")
      (node (ref "U$1") (pin "2A") (pinfunction "2A_2A") (pintype "output"))
      (node (ref "X-MOT") (pin "2") (pinfunction "2_2") (pintype "passive"))
      (node (ref "X-MOT") (pin "6") (pinfunction "6_6") (pintype "passive"))
    )
    (net (code "71") (name "Net-(U$1-Pad2B)") (class "Default")
      (node (ref "U$1") (pin "2B") (pinfunction "2B_2B") (pintype "output"))
      (node (ref "X-MOT") (pin "1") (pinfunction "1_1") (pintype "passive"))
      (node (ref "X-MOT") (pin "5") (pinfunction "5_5") (pintype "passive"))
    )
    (net (code "72") (name "Net-(U$1-SLEEP)") (class "Default")
      (node (ref "U$1") (pin "RST") (pinfunction "RST_RST") (pintype "input"))
      (node (ref "U$1") (pin "SLP") (pinfunction "SLEEP_SLP") (pintype "input"))
    )
    (net (code "73") (name "Net-(U$2-SLEEP)") (class "Default")
      (node (ref "U$2") (pin "RST") (pinfunction "RST_RST") (pintype "input"))
      (node (ref "U$2") (pin "SLP") (pinfunction "SLEEP_SLP") (pintype "input"))
    )
    (net (code "74") (name "Net-(U$3-Pad1A)") (class "Default")
      (node (ref "U$3") (pin "1A") (pinfunction "1A_1A") (pintype "output"))
      (node (ref "Y-MOT") (pin "3") (pinfunction "3_3") (pintype "passive"))
      (node (ref "Y-MOT") (pin "7") (pinfunction "7_7") (pintype "passive"))
    )
    (net (code "75") (name "Net-(U$3-Pad1B)") (class "Default")
      (node (ref "U$3") (pin "1B") (pinfunction "1B_1B") (pintype "output"))
      (node (ref "Y-MOT") (pin "4") (pinfunction "4_4") (pintype "passive"))
      (node (ref "Y-MOT") (pin "8") (pinfunction "8_8") (pintype "passive"))
    )
    (net (code "76") (name "Net-(U$3-Pad2A)") (class "Default")
      (node (ref "U$3") (pin "2A") (pinfunction "2A_2A") (pintype "output"))
      (node (ref "Y-MOT") (pin "2") (pinfunction "2_2") (pintype "passive"))
      (node (ref "Y-MOT") (pin "6") (pinfunction "6_6") (pintype "passive"))
    )
    (net (code "77") (name "Net-(U$3-Pad2B)") (class "Default")
      (node (ref "U$3") (pin "2B") (pinfunction "2B_2B") (pintype "output"))
      (node (ref "Y-MOT") (pin "1") (pinfunction "1_1") (pintype "passive"))
      (node (ref "Y-MOT") (pin "5") (pinfunction "5_5") (pintype "passive"))
    )
    (net (code "78") (name "Net-(U$3-SLEEP)") (class "Default")
      (node (ref "U$3") (pin "RST") (pinfunction "RST_RST") (pintype "input"))
      (node (ref "U$3") (pin "SLP") (pinfunction "SLEEP_SLP") (pintype "input"))
    )
    (net (code "79") (name "Net-(U$6-Pad1A)") (class "Default")
      (node (ref "U$6") (pin "1A") (pinfunction "1A_1A") (pintype "output"))
      (node (ref "Z-MOT1") (pin "3") (pinfunction "3_3") (pintype "passive"))
    )
    (net (code "80") (name "Net-(U$6-Pad1B)") (class "Default")
      (node (ref "U$6") (pin "1B") (pinfunction "1B_1B") (pintype "output"))
      (node (ref "Z-MOT1") (pin "4") (pinfunction "4_4") (pintype "passive"))
    )
    (net (code "81") (name "Net-(U$6-Pad2A)") (class "Default")
      (node (ref "U$6") (pin "2A") (pinfunction "2A_2A") (pintype "output"))
      (node (ref "Z-MOT1") (pin "2") (pinfunction "2_2") (pintype "passive"))
    )
    (net (code "82") (name "Net-(U$6-Pad2B)") (class "Default")
      (node (ref "U$6") (pin "2B") (pinfunction "2B_2B") (pintype "output"))
      (node (ref "Z-MOT1") (pin "1") (pinfunction "1_1") (pintype "passive"))
    )
    (net (code "83") (name "Net-(U$6-SLEEP)") (class "Default")
      (node (ref "U$6") (pin "RST") (pinfunction "RST_RST") (pintype "input"))
      (node (ref "U$6") (pin "SLP") (pinfunction "SLEEP_SLP") (pintype "input"))
    )
    (net (code "84") (name "Net-(U$9-Pad1A)") (class "Default")
      (node (ref "U$9") (pin "1A") (pinfunction "1A_1A") (pintype "output"))
      (node (ref "Z-MOT") (pin "3") (pinfunction "3_3") (pintype "passive"))
      (node (ref "Z-MOT") (pin "7") (pinfunction "7_7") (pintype "passive"))
    )
    (net (code "85") (name "Net-(U$9-Pad1B)") (class "Default")
      (node (ref "U$9") (pin "1B") (pinfunction "1B_1B") (pintype "output"))
      (node (ref "Z-MOT") (pin "4") (pinfunction "4_4") (pintype "passive"))
      (node (ref "Z-MOT") (pin "8") (pinfunction "8_8") (pintype "passive"))
    )
    (net (code "86") (name "Net-(U$9-Pad2A)") (class "Default")
      (node (ref "U$9") (pin "2A") (pinfunction "2A_2A") (pintype "output"))
      (node (ref "Z-MOT") (pin "2") (pinfunction "2_2") (pintype "passive"))
      (node (ref "Z-MOT") (pin "6") (pinfunction "6_6") (pintype "passive"))
    )
    (net (code "87") (name "Net-(U$9-Pad2B)") (class "Default")
      (node (ref "U$9") (pin "2B") (pinfunction "2B_2B") (pintype "output"))
      (node (ref "Z-MOT") (pin "1") (pinfunction "1_1") (pintype "passive"))
      (node (ref "Z-MOT") (pin "5") (pinfunction "5_5") (pintype "passive"))
    )
    (net (code "88") (name "Net-(U$9-SLEEP)") (class "Default")
      (node (ref "U$9") (pin "RST") (pinfunction "RST_RST") (pintype "input"))
      (node (ref "U$9") (pin "SLP") (pinfunction "SLEEP_SLP") (pintype "input"))
    )
    (net (code "89") (name "unconnected-(IC1-INTA-Pad20)") (class "Default")
      (node (ref "IC1") (pin "20") (pinfunction "INTA_20") (pintype "output"))
    )
    (net (code "90") (name "unconnected-(IC1-INTB-Pad19)") (class "Default")
      (node (ref "IC1") (pin "19") (pinfunction "INTB_19") (pintype "output"))
    )
    (net (code "91") (name "unconnected-(JP8-Pad1)") (class "Default")
      (node (ref "JP8") (pin "1") (pinfunction "1_1") (pintype "passive"))
    )
    (net (code "92") (name "unconnected-(LM1117-5V-OUT1-PadTAB)") (class "Default")
      (node (ref "LM1117-5V") (pin "TAB") (pinfunction "OUT1_TAB") (pintype "passive"))
    )
    (net (code "93") (name "unconnected-(LM1117-5V1-OUT1-PadTAB)") (class "Default")
      (node (ref "LM1117-5V1") (pin "TAB") (pinfunction "OUT1_TAB") (pintype "passive"))
    )
    (net (code "94") (name "unconnected-(U$5-PadRST)") (class "Default")
      (node (ref "U$5") (pin "RST") (pinfunction "RST_RST") (pintype "bidirectional"))
    )
    (net (code "95") (name "unconnected-(U$5-PadRX)") (class "Default")
      (node (ref "U$5") (pin "RX") (pinfunction "RX_RX") (pintype "bidirectional"))
    )
    (net (code "96") (name "unconnected-(U$5-PadTX)") (class "Default")
      (node (ref "U$5") (pin "TX") (pinfunction "TX_TX") (pintype "bidirectional"))
    )
  )
)
